# auc-step-generator.net
KiCad netlist of a schematic drawn in EAGLE
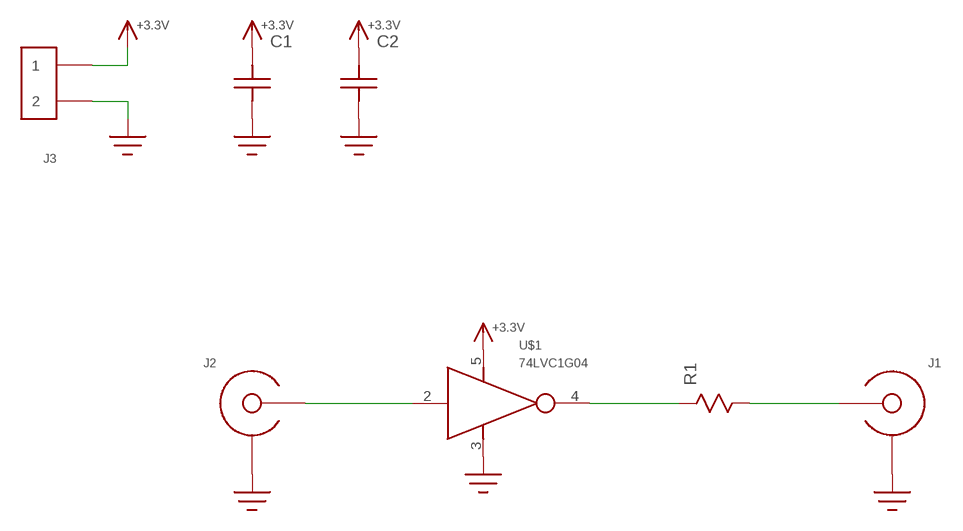
[diagram p0: schematic, sheet 1]

(export (version "E")
  (design (tool "Eeschema 10.0.6"))
  (components
    (comp (ref "C1")
      (value "C1206")
      (footprint "eagle-import:1206")
      (libsource (lib "eagle-import") (part "C1206"))
    )
    (comp (ref "C2")
      (value "C0603")
      (footprint "eagle-import:C0603")
      (libsource (lib "eagle-import") (part "C0603"))
    )
    (comp (ref "J1")
      (value "SMA-EDGE-LAUNCH4020_TAPER")
      (footprint "eagle-import:SMA_EDGE_LAUNCH_2L_4020_TAPER")
      (libsource (lib "eagle-import") (part "SMA-EDGE-LAUNCH4020_TAPER"))
    )
    (comp (ref "J2")
      (value "SMA-EDGE-LAUNCH4020_TAPER")
      (footprint "eagle-import:SMA_EDGE_LAUNCH_2L_4020_TAPER")
      (libsource (lib "eagle-import") (part "SMA-EDGE-LAUNCH4020_TAPER"))
    )
    (comp (ref "J3")
      (value "HEADER_2PIN")
      (footprint "eagle-import:HEADER_2PIN")
      (libsource (lib "eagle-import") (part "HEADER_2PIN"))
    )
    (comp (ref "R1")
      (value "R0603")
      (footprint "eagle-import:R0603")
      (libsource (lib "eagle-import") (part "R0603"))
    )
    (comp (ref "U$1")
      (value "74LVC1G04")
      (footprint "eagle-import:SOT23-5")
      (libsource (lib "eagle-import") (part "74LVC1G04"))
    )
  )
  (nets
    (net (code "1") (name "+3.3V") (class "Default")
      (node (ref "C1") (pin "P$2") (pinfunction "P$2_P$2") (pintype "bidirectional"))
      (node (ref "C2") (pin "P$2") (pinfunction "P$2_P$2") (pintype "bidirectional"))
      (node (ref "J3") (pin "1") (pinfunction "1_1") (pintype "bidirectional"))
      (node (ref "U$1") (pin "5") (pinfunction "VCC_5") (pintype "bidirectional"))
    )
    (net (code "2") (name "GND") (class "Default")
      (node (ref "C1") (pin "P$1") (pinfunction "P$1_P$1") (pintype "bidirectional"))
      (node (ref "C2") (pin "P$1") (pinfunction "P$1_P$1") (pintype "bidirectional"))
      (node (ref "J1") (pin "BOTTOM_GND") (pinfunction "SHIELD_BOTTOM_GND") (pintype "bidirectional"))
      (node (ref "J1") (pin "GND@1") (pinfunction "SHIELD_GND@1") (pintype "bidirectional"))
      (node (ref "J1") (pin "GND@14") (pinfunction "SHIELD_GND@14") (pintype "bidirectional"))
      (node (ref "J1") (pin "GND@15") (pinfunction "SHIELD_GND@15") (pintype "bidirectional"))
      (node (ref "J1") (pin "GND@16") (pinfunction "SHIELD_GND@16") (pintype "bidirectional"))
      (node (ref "J1") (pin "GND@17") (pinfunction "SHIELD_GND@17") (pintype "bidirectional"))
      (node (ref "J1") (pin "GND@2") (pinfunction "SHIELD_GND@2") (pintype "bidirectional"))
      (node (ref "J1") (pin "GND@3") (pinfunction "SHIELD_GND@3") (pintype "bidirectional"))
      (node (ref "J1") (pin "GND@4") (pinfunction "SHIELD_GND@4") (pintype "bidirectional"))
      (node (ref "J1") (pin "GND@5") (pinfunction "SHIELD_GND@5") (pintype "bidirectional"))
      (node (ref "J1") (pin "GND@6") (pinfunction "SHIELD_GND@6") (pintype "bidirectional"))
      (node (ref "J1") (pin "GND@7") (pinfunction "SHIELD_GND@7") (pintype "bidirectional"))
      (node (ref "J1") (pin "GND@8") (pinfunction "SHIELD_GND@8") (pintype "bidirectional"))
      (node (ref "J1") (pin "GND_PAD1") (pinfunction "SHIELD_GND_PAD1") (pintype "bidirectional"))
      (node (ref "J1") (pin "GND_PAD2") (pinfunction "SHIELD_GND_PAD2") (pintype "bidirectional"))
      (node (ref "J1") (pin "P$1") (pinfunction "SHIELD_P$1") (pintype "bidirectional"))
      (node (ref "J1") (pin "P$2") (pinfunction "SHIELD_P$2") (pintype "bidirectional"))
      (node (ref "J2") (pin "BOTTOM_GND") (pinfunction "SHIELD_BOTTOM_GND") (pintype "bidirectional"))
      (node (ref "J2") (pin "GND@1") (pinfunction "SHIELD_GND@1") (pintype "bidirectional"))
      (node (ref "J2") (pin "GND@14") (pinfunction "SHIELD_GND@14") (pintype "bidirectional"))
      (node (ref "J2") (pin "GND@15") (pinfunction "SHIELD_GND@15") (pintype "bidirectional"))
      (node (ref "J2") (pin "GND@16") (pinfunction "SHIELD_GND@16") (pintype "bidirectional"))
      (node (ref "J2") (pin "GND@17") (pinfunction "SHIELD_GND@17") (pintype "bidirectional"))
      (node (ref "J2") (pin "GND@2") (pinfunction "SHIELD_GND@2") (pintype "bidirectional"))
      (node (ref "J2") (pin "GND@3") (pinfunction "SHIELD_GND@3") (pintype "bidirectional"))
      (node (ref "J2") (pin "GND@4") (pinfunction "SHIELD_GND@4") (pintype "bidirectional"))
      (node (ref "J2") (pin "GND@5") (pinfunction "SHIELD_GND@5") (pintype "bidirectional"))
      (node (ref "J2") (pin "GND@6") (pinfunction "SHIELD_GND@6") (pintype "bidirectional"))
      (node (ref "J2") (pin "GND@7") (pinfunction "SHIELD_GND@7") (pintype "bidirectional"))
      (node (ref "J2") (pin "GND@8") (pinfunction "SHIELD_GND@8") (pintype "bidirectional"))
      (node (ref "J2") (pin "GND_PAD1") (pinfunction "SHIELD_GND_PAD1") (pintype "bidirectional"))
      (node (ref "J2") (pin "GND_PAD2") (pinfunction "SHIELD_GND_PAD2") (pintype "bidirectional"))
      (node (ref "J2") (pin "P$1") (pinfunction "SHIELD_P$1") (pintype "bidirectional"))
      (node (ref "J2") (pin "P$2") (pinfunction "SHIELD_P$2") (pintype "bidirectional"))
      (node (ref "J3") (pin "2") (pinfunction "2_2") (pintype "bidirectional"))
      (node (ref "U$1") (pin "3") (pinfunction "GND_3") (pintype "bidirectional"))
    )
    (net (code "3") (name "Net-(J1-CENTER)") (class "Default")
      (node (ref "J1") (pin "CENTER@1") (pinfunction "CENTER_CENTER@1") (pintype "bidirectional"))
      (node (ref "R1") (pin "P$2") (pinfunction "P$4_P$2") (pintype "bidirectional"))
    )
    (net (code "4") (name "Net-(J2-CENTER)") (class "Default")
      (node (ref "J2") (pin "CENTER@1") (pinfunction "CENTER_CENTER@1") (pintype "bidirectional"))
      (node (ref "U$1") (pin "2") (pinfunction "IN_2") (pintype "bidirectional"))
    )
    (net (code "5") (name "Net-(R1-P$3)") (class "Default")
      (node (ref "R1") (pin "P$1") (pinfunction "P$3_P$1") (pintype "bidirectional"))
      (node (ref "U$1") (pin "4") (pinfunction "OUT_4") (pintype "bidirectional"))
    )
  )
)
